# IMU_breakout.net
KiCad netlist of a schematic drawn in EAGLE
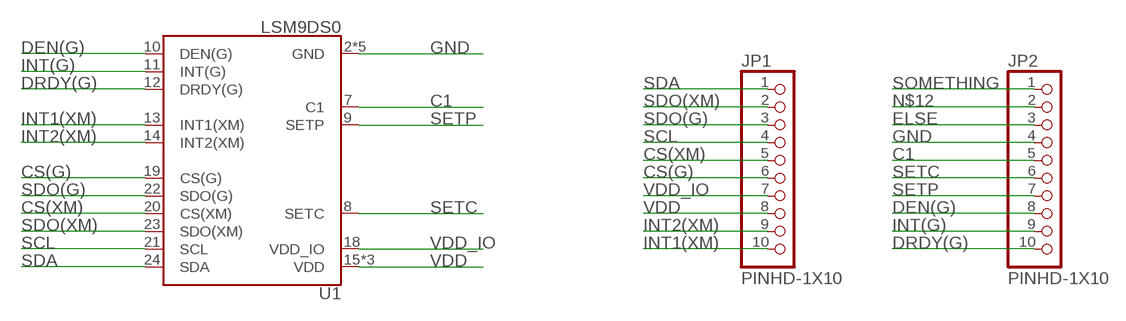
[diagram p0: schematic, sheet 1]

(export (version "E")
  (design (tool "Eeschema 10.0.6"))
  (components
    (comp (ref "JP1")
      (value "PINHD-1X10")
      (footprint "eagle-import:1X10-BIG")
      (libsource (lib "eagle-import") (part "PINHD-1X10"))
    )
    (comp (ref "JP2")
      (value "PINHD-1X10")
      (footprint "eagle-import:1X10-BIG")
      (libsource (lib "eagle-import") (part "PINHD-1X10"))
    )
    (comp (ref "U1")
      (value "LSM9DS0")
      (footprint "eagle-import:LGA-24")
      (libsource (lib "eagle-import") (part "LSM9DS0"))
    )
  )
  (nets
    (net (code "1") (name "/C1") (class "Default")
      (node (ref "JP2") (pin "5") (pinfunction "5_5") (pintype "passive"))
      (node (ref "U1") (pin "7") (pinfunction "C1_7") (pintype "bidirectional"))
    )
    (net (code "2") (name "/CS(G)") (class "Default")
      (node (ref "JP1") (pin "6") (pinfunction "6_6") (pintype "passive"))
      (node (ref "U1") (pin "19") (pinfunction "CS(G)_19") (pintype "bidirectional"))
    )
    (net (code "3") (name "/CS(XM)") (class "Default")
      (node (ref "JP1") (pin "5") (pinfunction "5_5") (pintype "passive"))
      (node (ref "U1") (pin "20") (pinfunction "CS(XM)_20") (pintype "bidirectional"))
    )
    (net (code "4") (name "/DEN(G)") (class "Default")
      (node (ref "JP2") (pin "8") (pinfunction "8_8") (pintype "passive"))
      (node (ref "U1") (pin "10") (pinfunction "DEN(G)_10") (pintype "bidirectional"))
    )
    (net (code "5") (name "/DRDY(G)") (class "Default")
      (node (ref "JP2") (pin "10") (pinfunction "10_10") (pintype "passive"))
      (node (ref "U1") (pin "12") (pinfunction "DRDY(G)_12") (pintype "bidirectional"))
    )
    (net (code "6") (name "/ELSE") (class "Default")
      (node (ref "JP2") (pin "3") (pinfunction "3_3") (pintype "passive"))
    )
    (net (code "7") (name "/GND") (class "Default")
      (node (ref "JP2") (pin "4") (pinfunction "4_4") (pintype "passive"))
      (node (ref "U1") (pin "2") (pinfunction "GND_2") (pintype "bidirectional"))
      (node (ref "U1") (pin "3") (pinfunction "GND_3") (pintype "bidirectional"))
      (node (ref "U1") (pin "4") (pinfunction "GND_4") (pintype "bidirectional"))
      (node (ref "U1") (pin "5") (pinfunction "GND_5") (pintype "bidirectional"))
      (node (ref "U1") (pin "6") (pinfunction "GND_6") (pintype "bidirectional"))
    )
    (net (code "8") (name "/INT(G)") (class "Default")
      (node (ref "JP2") (pin "9") (pinfunction "9_9") (pintype "passive"))
      (node (ref "U1") (pin "11") (pinfunction "INT(G)_11") (pintype "bidirectional"))
    )
    (net (code "9") (name "/INT1(XM)") (class "Default")
      (node (ref "JP1") (pin "10") (pinfunction "10_10") (pintype "passive"))
      (node (ref "U1") (pin "13") (pinfunction "INT1(XM)_13") (pintype "bidirectional"))
    )
    (net (code "10") (name "/INT2(XM)") (class "Default")
      (node (ref "JP1") (pin "9") (pinfunction "9_9") (pintype "passive"))
      (node (ref "U1") (pin "14") (pinfunction "INT2(XM)_14") (pintype "bidirectional"))
    )
    (net (code "11") (name "/N$12") (class "Default")
      (node (ref "JP2") (pin "2") (pinfunction "2_2") (pintype "passive"))
    )
    (net (code "12") (name "/SCL") (class "Default")
      (node (ref "JP1") (pin "4") (pinfunction "4_4") (pintype "passive"))
      (node (ref "U1") (pin "21") (pinfunction "SCL_21") (pintype "bidirectional"))
    )
    (net (code "13") (name "/SDA") (class "Default")
      (node (ref "JP1") (pin "1") (pinfunction "1_1") (pintype "passive"))
      (node (ref "U1") (pin "24") (pinfunction "SDA_24") (pintype "bidirectional"))
    )
    (net (code "14") (name "/SDO(G)") (class "Default")
      (node (ref "JP1") (pin "3") (pinfunction "3_3") (pintype "passive"))
      (node (ref "U1") (pin "22") (pinfunction "SDO(G)_22") (pintype "bidirectional"))
    )
    (net (code "15") (name "/SDO(XM)") (class "Default")
      (node (ref "JP1") (pin "2") (pinfunction "2_2") (pintype "passive"))
      (node (ref "U1") (pin "23") (pinfunction "SDO(XM)_23") (pintype "bidirectional"))
    )
    (net (code "16") (name "/SETC") (class "Default")
      (node (ref "JP2") (pin "6") (pinfunction "6_6") (pintype "passive"))
      (node (ref "U1") (pin "8") (pinfunction "SETC_8") (pintype "bidirectional"))
    )
    (net (code "17") (name "/SETP") (class "Default")
      (node (ref "JP2") (pin "7") (pinfunction "7_7") (pintype "passive"))
      (node (ref "U1") (pin "9") (pinfunction "SETP_9") (pintype "bidirectional"))
    )
    (net (code "18") (name "/SOMETHING") (class "Default")
      (node (ref "JP2") (pin "1") (pinfunction "1_1") (pintype "passive"))
    )
    (net (code "19") (name "/VDD") (class "Default")
      (node (ref "JP1") (pin "8") (pinfunction "8_8") (pintype "passive"))
      (node (ref "U1") (pin "15") (pinfunction "VDD_15") (pintype "bidirectional"))
      (node (ref "U1") (pin "16") (pinfunction "VDD_16") (pintype "bidirectional"))
      (node (ref "U1") (pin "17") (pinfunction "VDD_17") (pintype "bidirectional"))
    )
    (net (code "20") (name "/VDD_IO") (class "Default")
      (node (ref "JP1") (pin "7") (pinfunction "7_7") (pintype "passive"))
      (node (ref "U1") (pin "18") (pinfunction "VDD_IO_18") (pintype "bidirectional"))
    )
  )
)
